# main_board_v1_0.net
KiCad netlist of a schematic drawn in EAGLE
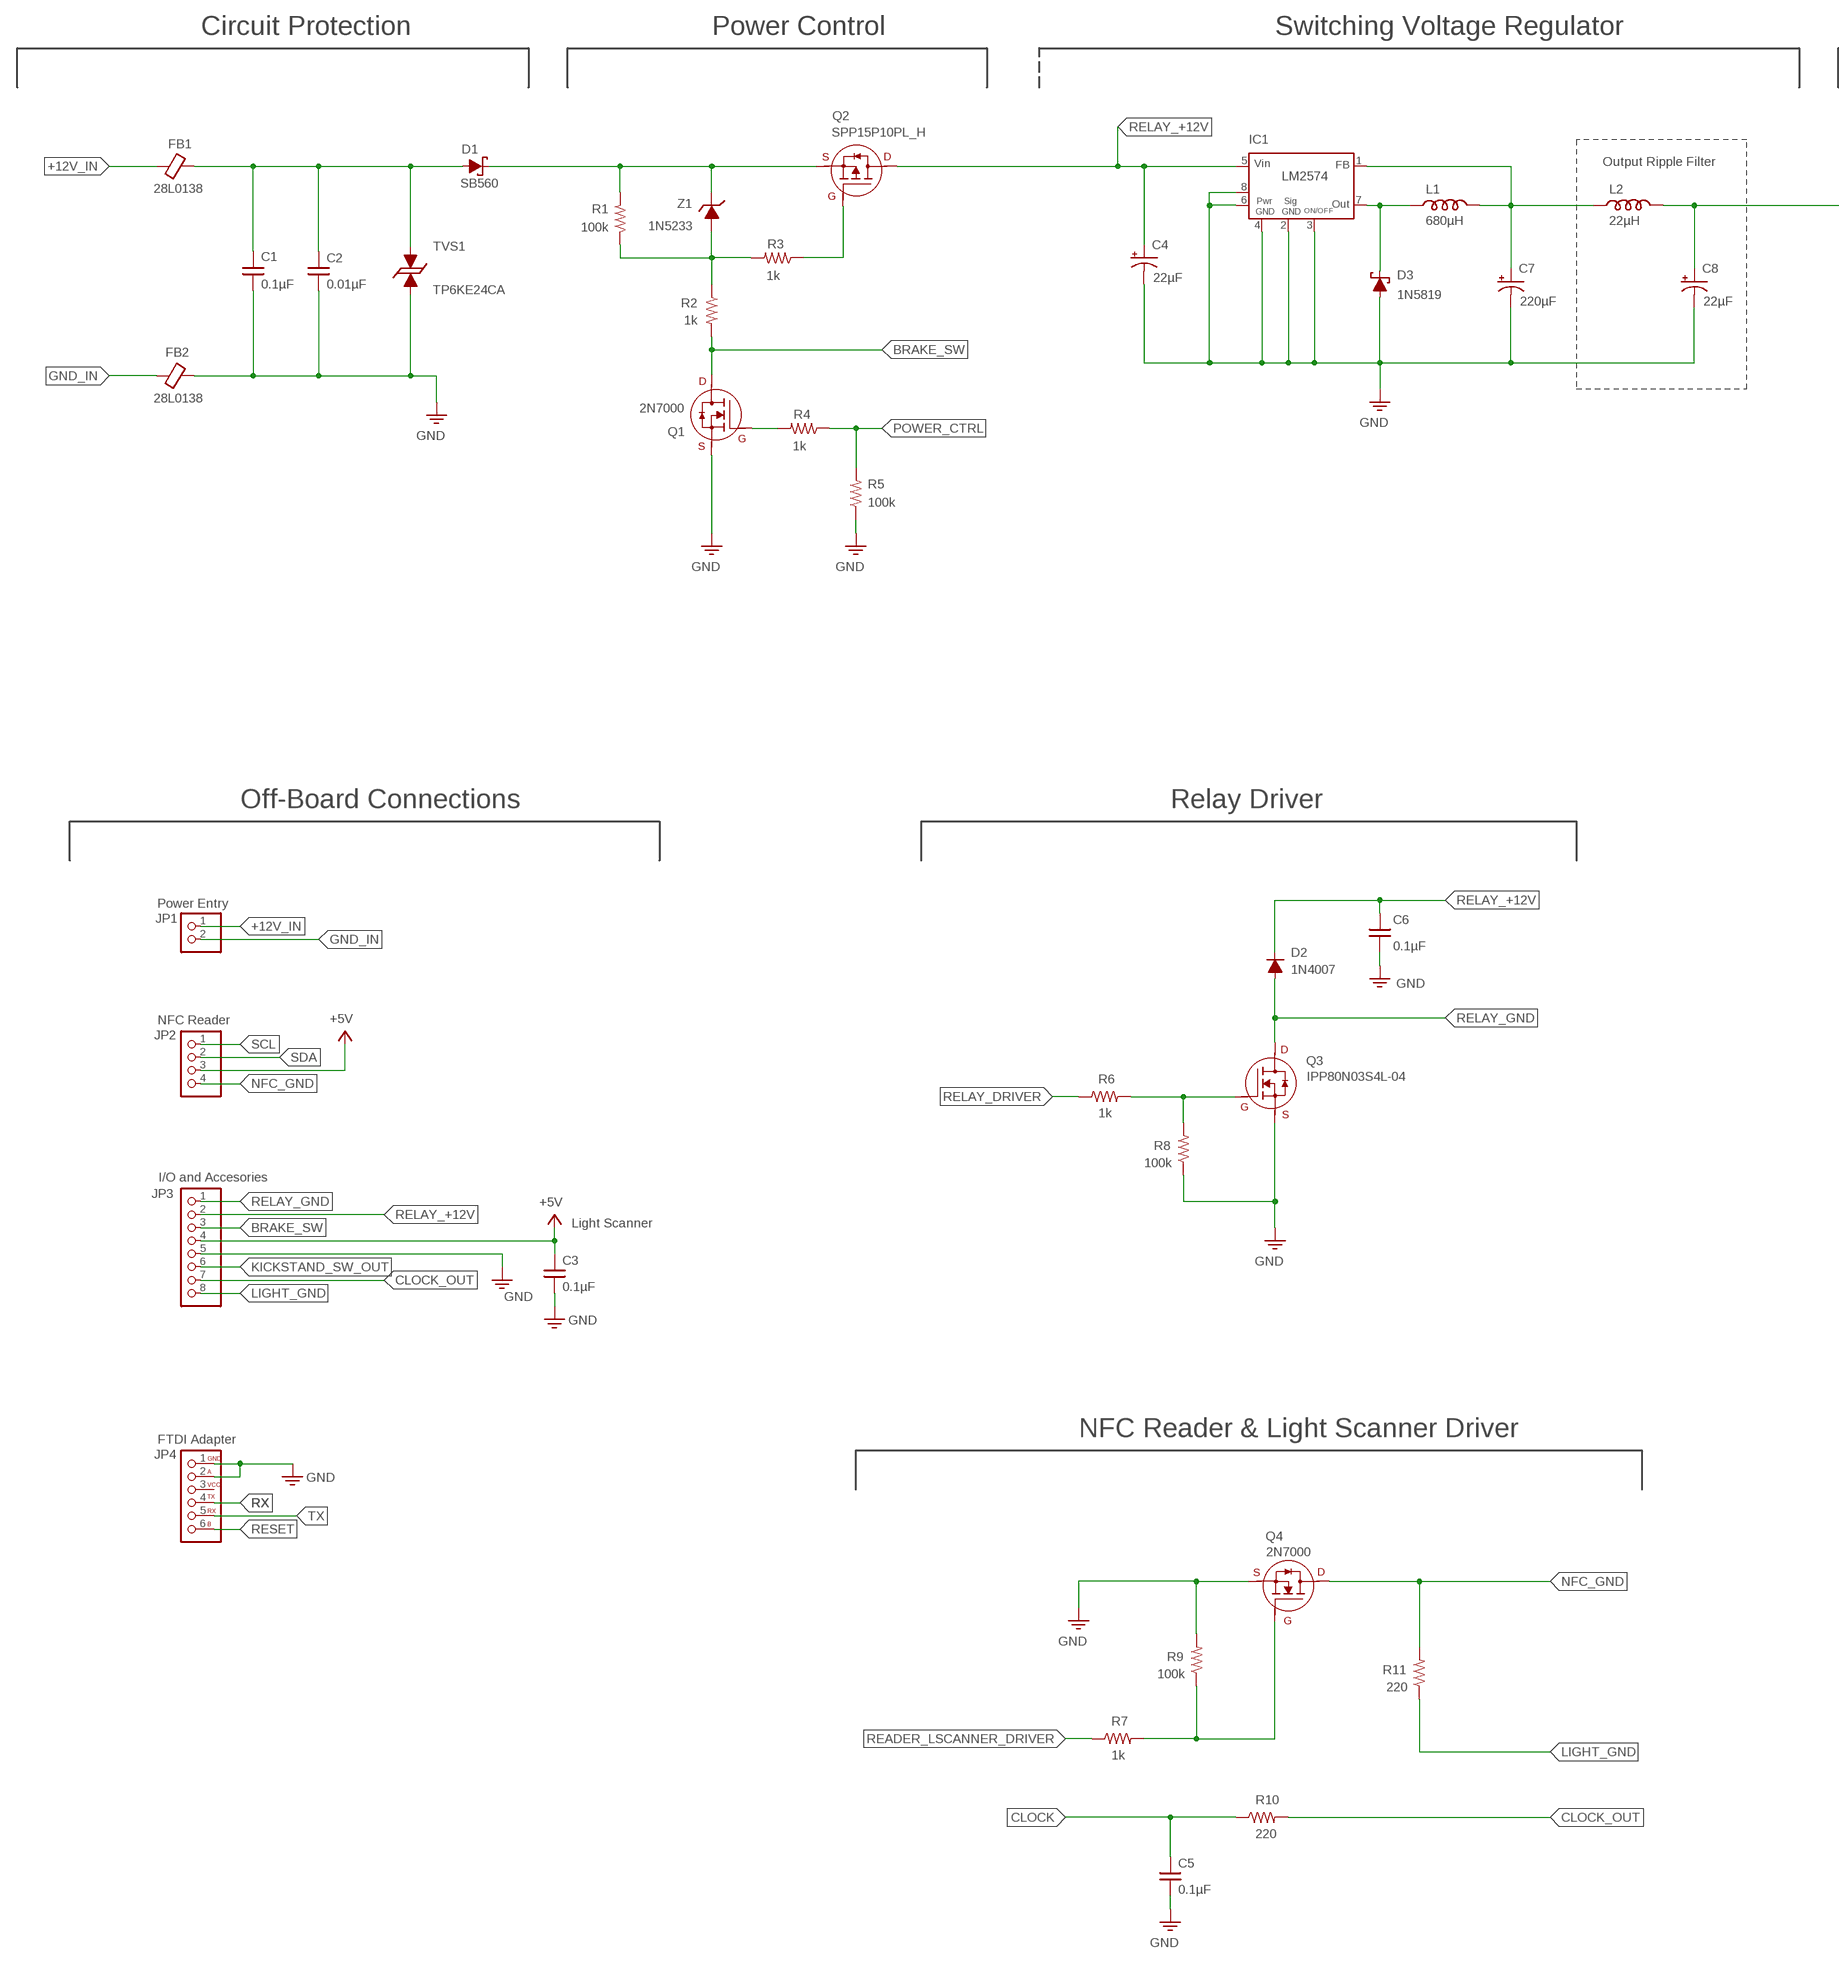
[diagram p0: schematic, sheet 1, part 1 of 2]
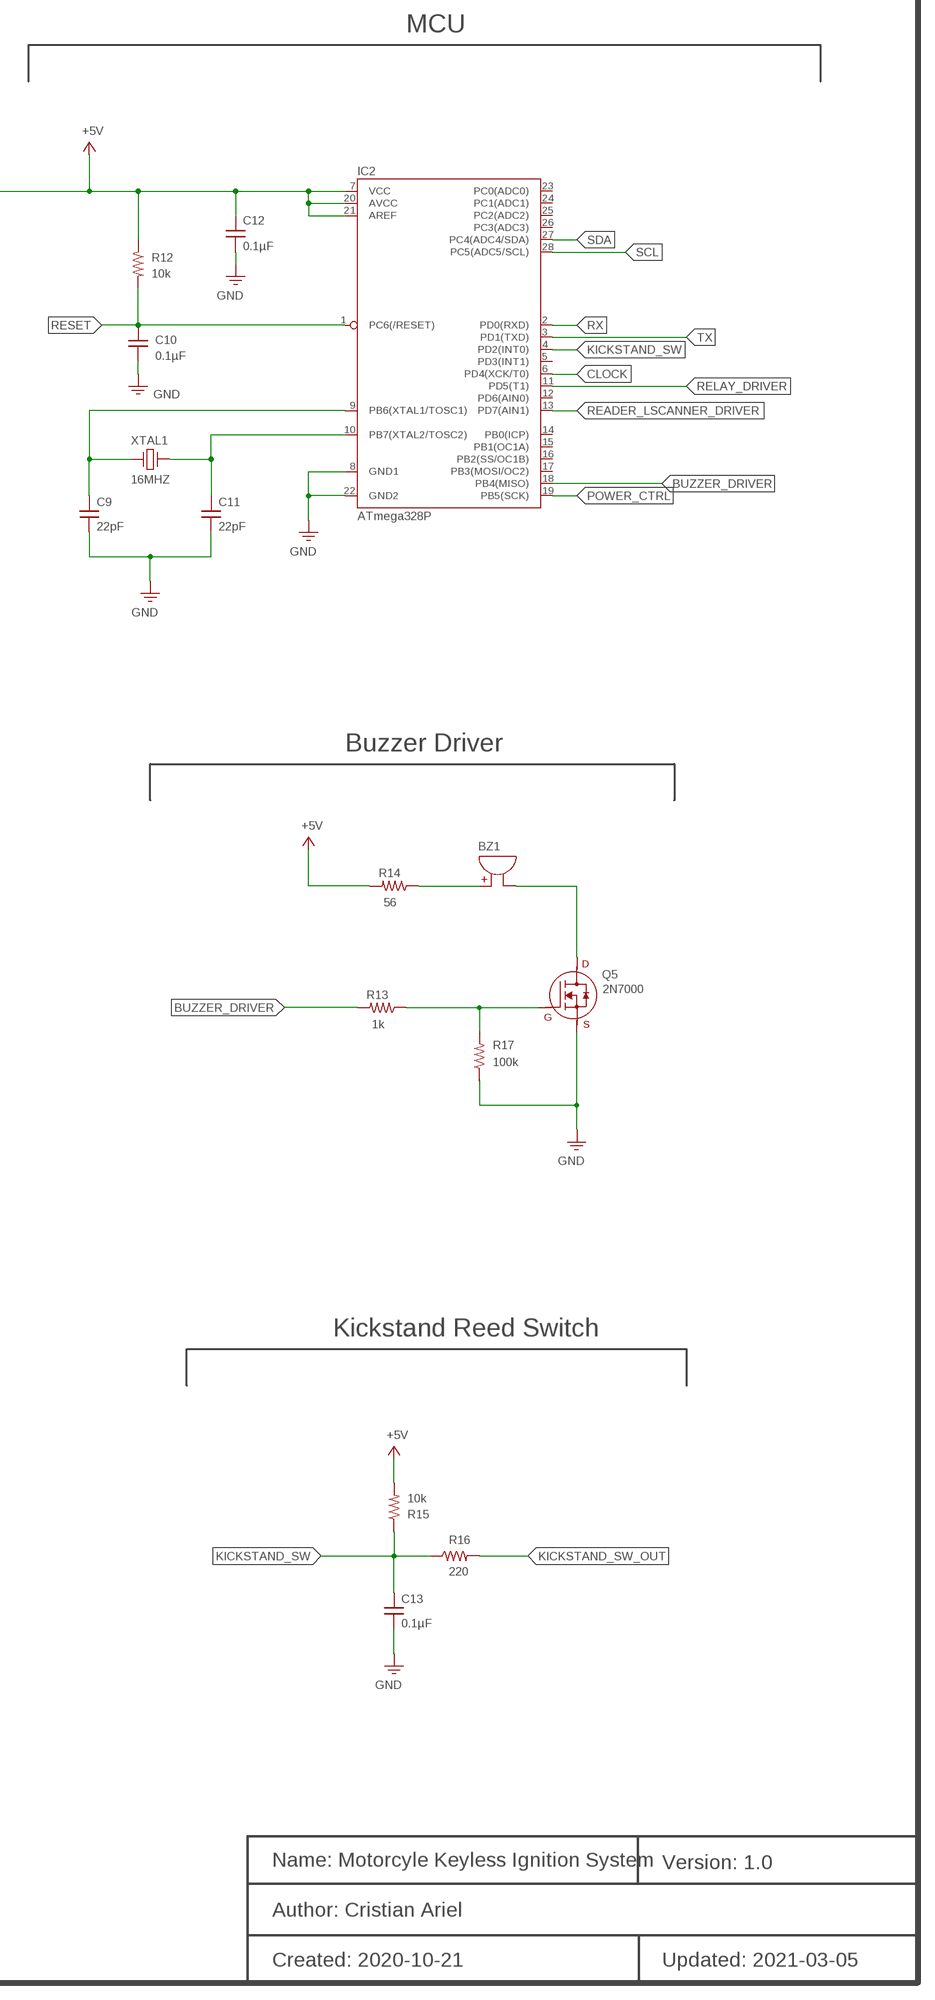
[diagram p1: schematic, sheet 1, part 2 of 2]

(export (version "E")
  (design (tool "Eeschema 10.0.6"))
  (components
    (comp (ref "BZ1")
      (value "BUZZER_254-EMB15-RO")
      (footprint "eagle-import:BUZZER-12")
      (libsource (lib "eagle-import") (part "BUZZER_254-EMB15-RO"))
    )
    (comp (ref "C1")
      (value "0.1µF")
      (footprint "eagle-import:C_H5")
      (libsource (lib "eagle-import") (part "C_K104K15X7RF53H5_0.1µF"))
    )
    (comp (ref "C2")
      (value "0.01µF")
      (footprint "eagle-import:C_H5")
      (libsource (lib "eagle-import") (part "C_FA24NP02E103JNU06_0.01µF"))
    )
    (comp (ref "C3")
      (value "0.1µF")
      (footprint "eagle-import:C_H5")
      (libsource (lib "eagle-import") (part "C_K104K15X7RF53H5_0.1µF"))
    )
    (comp (ref "C4")
      (value "22µF")
      (footprint "eagle-import:C_UBT_8")
      (libsource (lib "eagle-import") (part "C_POLARIZED_UBT1H220MPD_22µF"))
    )
    (comp (ref "C5")
      (value "0.1µF")
      (footprint "eagle-import:C_H5")
      (libsource (lib "eagle-import") (part "C_K104K15X7RF53H5_0.1µF"))
    )
    (comp (ref "C6")
      (value "0.1µF")
      (footprint "eagle-import:C_H5")
      (libsource (lib "eagle-import") (part "C_K104K15X7RF53H5_0.1µF"))
    )
    (comp (ref "C7")
      (value "220µF")
      (footprint "eagle-import:C_UBT_10")
      (libsource (lib "eagle-import") (part "C_POLARIZED_UBT1C221MPD_220µF"))
    )
    (comp (ref "C8")
      (value "22µF")
      (footprint "eagle-import:C_UBT_8")
      (libsource (lib "eagle-import") (part "C_POLARIZED_UBT1H220MPD_22µF"))
    )
    (comp (ref "C9")
      (value "22pF")
      (footprint "eagle-import:C_H5")
      (libsource (lib "eagle-import") (part "C_K220J10C0GF5UH5_22PF"))
    )
    (comp (ref "C10")
      (value "0.1µF")
      (footprint "eagle-import:C_H5")
      (libsource (lib "eagle-import") (part "C_K104K15X7RF53H5_0.1µF"))
    )
    (comp (ref "C11")
      (value "22pF")
      (footprint "eagle-import:C_H5")
      (libsource (lib "eagle-import") (part "C_K220J10C0GF5UH5_22PF"))
    )
    (comp (ref "C12")
      (value "0.1µF")
      (footprint "eagle-import:C_H5")
      (libsource (lib "eagle-import") (part "C_K104K15X7RF53H5_0.1µF"))
    )
    (comp (ref "C13")
      (value "0.1µF")
      (footprint "eagle-import:C_H5")
      (libsource (lib "eagle-import") (part "C_K104K15X7RF53H5_0.1µF"))
    )
    (comp (ref "D1")
      (value "SB560")
      (footprint "eagle-import:DO-201AD")
      (libsource (lib "eagle-import") (part "D_SCHOTTKY_SB560"))
    )
    (comp (ref "D2")
      (value "1N4007")
      (footprint "eagle-import:DO-41_(DO-204AL)")
      (libsource (lib "eagle-import") (part "D_1N4007"))
    )
    (comp (ref "D3")
      (value "1N5819")
      (footprint "eagle-import:DO-204AL_(DO-41)")
      (libsource (lib "eagle-import") (part "D_SCHOTTKY_1N5819"))
    )
    (comp (ref "FB1")
      (value "28L0138")
      (footprint "eagle-import:FB-5.23")
      (libsource (lib "eagle-import") (part "FERRITE_BEAD_28L0138"))
    )
    (comp (ref "FB2")
      (value "28L0138")
      (footprint "eagle-import:FB-5.23")
      (libsource (lib "eagle-import") (part "FERRITE_BEAD_28L0138"))
    )
    (comp (ref "IC1")
      (value "LM2574")
      (footprint "eagle-import:DIL08")
      (libsource (lib "eagle-import") (part "SWITCHING_REG_8_LM2574"))
    )
    (comp (ref "IC2")
      (value "ATmega328P")
      (footprint "eagle-import:DIP28")
      (libsource (lib "eagle-import") (part "ATMEGA328P_PDIP"))
    )
    (comp (ref "JP1")
      (value "Power Entry")
      (footprint "eagle-import:1X021")
      (libsource (lib "eagle-import") (part "PINHD-1X2"))
    )
    (comp (ref "JP2")
      (value "NFC Reader")
      (footprint "eagle-import:KK254_1X4")
      (libsource (lib "eagle-import") (part "KK254_1X4"))
    )
    (comp (ref "JP3")
      (value "I/O and Accesories")
      (footprint "eagle-import:1X08")
      (libsource (lib "eagle-import") (part "PINHD-1X8"))
    )
    (comp (ref "JP4")
      (value "FTDI Adapter")
      (footprint "eagle-import:1X06_FTDI")
      (libsource (lib "eagle-import") (part "FTDI_6"))
    )
    (comp (ref "L1")
      (value "680µH")
      (footprint "eagle-import:PE-526")
      (libsource (lib "eagle-import") (part "INDUCTOR_PE-52629NL_680µH"))
    )
    (comp (ref "L2")
      (value "22µH")
      (footprint "eagle-import:LTF-D")
      (libsource (lib "eagle-import") (part "INDUCTOR_LTF5022-D_22µH"))
    )
    (comp (ref "Q1")
      (value "2N7000")
      (footprint "eagle-import:TO-92")
      (libsource (lib "eagle-import") (part "MOSFET_NCH_V_2N7000"))
    )
    (comp (ref "Q2")
      (value "SPP15P10PL_H")
      (footprint "eagle-import:TO220")
      (libsource (lib "eagle-import") (part "MOSFET_PCH_H_SPP15P10PL_H"))
    )
    (comp (ref "Q3")
      (value "IPP80N03S4L-04")
      (footprint "eagle-import:TO220")
      (libsource (lib "eagle-import") (part "MOSFET_NCH_V_IPP80N03S4L-04"))
    )
    (comp (ref "Q4")
      (value "2N7000")
      (footprint "eagle-import:TO-92")
      (libsource (lib "eagle-import") (part "MOSFET_NCH_H_2N7000"))
    )
    (comp (ref "Q5")
      (value "2N7000")
      (footprint "eagle-import:TO-92")
      (libsource (lib "eagle-import") (part "MOSFET_NCH_V_2N7000"))
    )
    (comp (ref "R1")
      (value "100k")
      (footprint "eagle-import:R_THM")
      (libsource (lib "eagle-import") (part "R_THM"))
    )
    (comp (ref "R2")
      (value "1k")
      (footprint "eagle-import:R_THM")
      (libsource (lib "eagle-import") (part "R_THM"))
    )
    (comp (ref "R3")
      (value "1k")
      (footprint "eagle-import:R_THM")
      (libsource (lib "eagle-import") (part "R_THM"))
    )
    (comp (ref "R4")
      (value "1k")
      (footprint "eagle-import:R_THM")
      (libsource (lib "eagle-import") (part "R_THM"))
    )
    (comp (ref "R5")
      (value "100k")
      (footprint "eagle-import:R_THM")
      (libsource (lib "eagle-import") (part "R_THM"))
    )
    (comp (ref "R6")
      (value "1k")
      (footprint "eagle-import:R_THM")
      (libsource (lib "eagle-import") (part "R_THM"))
    )
    (comp (ref "R7")
      (value "1k")
      (footprint "eagle-import:R_THM")
      (libsource (lib "eagle-import") (part "R_THM"))
    )
    (comp (ref "R8")
      (value "100k")
      (footprint "eagle-import:R_THM")
      (libsource (lib "eagle-import") (part "R_THM"))
    )
    (comp (ref "R9")
      (value "100k")
      (footprint "eagle-import:R_THM")
      (libsource (lib "eagle-import") (part "R_THM"))
    )
    (comp (ref "R10")
      (value "220")
      (footprint "eagle-import:R_THM")
      (libsource (lib "eagle-import") (part "R_THM"))
    )
    (comp (ref "R11")
      (value "220")
      (footprint "eagle-import:R_THM")
      (libsource (lib "eagle-import") (part "R_THM"))
    )
    (comp (ref "R12")
      (value "10k")
      (footprint "eagle-import:R_THM")
      (libsource (lib "eagle-import") (part "R_THM"))
    )
    (comp (ref "R13")
      (value "1k")
      (footprint "eagle-import:R_THM")
      (libsource (lib "eagle-import") (part "R_THM"))
    )
    (comp (ref "R14")
      (value "56")
      (footprint "eagle-import:R_THM")
      (libsource (lib "eagle-import") (part "R_THM"))
    )
    (comp (ref "R15")
      (value "10k")
      (footprint "eagle-import:R_THM")
      (libsource (lib "eagle-import") (part "R_THM"))
    )
    (comp (ref "R16")
      (value "220")
      (footprint "eagle-import:R_THM")
      (libsource (lib "eagle-import") (part "R_THM"))
    )
    (comp (ref "R17")
      (value "100k")
      (footprint "eagle-import:R_THM")
      (libsource (lib "eagle-import") (part "R_THM"))
    )
    (comp (ref "TVS1")
      (value "TP6KE24CA")
      (footprint "eagle-import:DO-204AC_(DO-15)")
      (libsource (lib "eagle-import") (part "D_TVS_BI_P6KE24CA"))
    )
    (comp (ref "XTAL1")
      (value "16MHZ")
      (footprint "eagle-import:HC-49USX")
      (libsource (lib "eagle-import") (part "CRYSTAL_ECS-160-20-4X-DU_16MHZ"))
    )
    (comp (ref "Z1")
      (value "1N5233")
      (footprint "eagle-import:DO35-7A_ZENER")
      (libsource (lib "eagle-import") (part "D_ZENER_1N5233_6V"))
    )
  )
  (nets
    (net (code "1") (name "+5V") (class "Default")
      (node (ref "C12") (pin "1") (pinfunction "1_1") (pintype "passive"))
      (node (ref "C3") (pin "1") (pinfunction "1_1") (pintype "passive"))
      (node (ref "C8") (pin "+") (pinfunction "+_+") (pintype "passive"))
      (node (ref "IC2") (pin "20") (pinfunction "AVCC_20") (pintype "bidirectional"))
      (node (ref "IC2") (pin "21") (pinfunction "AREF_21") (pintype "bidirectional"))
      (node (ref "IC2") (pin "7") (pinfunction "VCC_7") (pintype "bidirectional"))
      (node (ref "JP2") (pin "3") (pinfunction "3_3") (pintype "passive"))
      (node (ref "JP3") (pin "4") (pinfunction "4_4") (pintype "passive"))
      (node (ref "L2") (pin "1") (pinfunction "END_1") (pintype "bidirectional"))
      (node (ref "R12") (pin "1") (pinfunction "1_1") (pintype "passive"))
      (node (ref "R14") (pin "2") (pinfunction "2_2") (pintype "passive"))
      (node (ref "R15") (pin "2") (pinfunction "2_2") (pintype "passive"))
    )
    (net (code "2") (name "+12V_IN") (class "Default")
      (node (ref "FB1") (pin "1") (pinfunction "1_1") (pintype "passive"))
      (node (ref "JP1") (pin "1") (pinfunction "1_1") (pintype "passive"))
    )
    (net (code "3") (name "BRAKE_SW") (class "Default")
      (node (ref "JP3") (pin "3") (pinfunction "3_3") (pintype "passive"))
      (node (ref "Q1") (pin "3") (pinfunction "D_3") (pintype "bidirectional"))
      (node (ref "R2") (pin "2") (pinfunction "2_2") (pintype "passive"))
    )
    (net (code "4") (name "BUZZER_DRIVER") (class "Default")
      (node (ref "IC2") (pin "18") (pinfunction "PB4(MISO)_18") (pintype "bidirectional"))
      (node (ref "R13") (pin "2") (pinfunction "2_2") (pintype "passive"))
    )
    (net (code "5") (name "CLOCK") (class "Default")
      (node (ref "C5") (pin "1") (pinfunction "1_1") (pintype "passive"))
      (node (ref "IC2") (pin "6") (pinfunction "PD4(XCK/T0)_6") (pintype "bidirectional"))
      (node (ref "R10") (pin "1") (pinfunction "1_1") (pintype "passive"))
    )
    (net (code "6") (name "CLOCK_OUT") (class "Default")
      (node (ref "JP3") (pin "7") (pinfunction "7_7") (pintype "passive"))
      (node (ref "R10") (pin "2") (pinfunction "2_2") (pintype "passive"))
    )
    (net (code "7") (name "GND") (class "Default")
      (node (ref "C1") (pin "2") (pinfunction "2_2") (pintype "passive"))
      (node (ref "C10") (pin "2") (pinfunction "2_2") (pintype "passive"))
      (node (ref "C11") (pin "2") (pinfunction "2_2") (pintype "passive"))
      (node (ref "C12") (pin "2") (pinfunction "2_2") (pintype "passive"))
      (node (ref "C13") (pin "2") (pinfunction "2_2") (pintype "passive"))
      (node (ref "C2") (pin "2") (pinfunction "2_2") (pintype "passive"))
      (node (ref "C3") (pin "2") (pinfunction "2_2") (pintype "passive"))
      (node (ref "C4") (pin "-") (pinfunction "-_-") (pintype "passive"))
      (node (ref "C5") (pin "2") (pinfunction "2_2") (pintype "passive"))
      (node (ref "C6") (pin "2") (pinfunction "2_2") (pintype "passive"))
      (node (ref "C7") (pin "-") (pinfunction "-_-") (pintype "passive"))
      (node (ref "C8") (pin "-") (pinfunction "-_-") (pintype "passive"))
      (node (ref "C9") (pin "2") (pinfunction "2_2") (pintype "passive"))
      (node (ref "D3") (pin "A") (pinfunction "A_A") (pintype "passive"))
      (node (ref "FB2") (pin "2") (pinfunction "2_2") (pintype "passive"))
      (node (ref "IC1") (pin "2") (pinfunction "SIG_GND_2") (pintype "bidirectional"))
      (node (ref "IC1") (pin "3") (pinfunction "ON/OFF_3") (pintype "bidirectional"))
      (node (ref "IC1") (pin "4") (pinfunction "PWR_GND_4") (pintype "bidirectional"))
      (node (ref "IC1") (pin "6") (pinfunction "P$1_6") (pintype "bidirectional"))
      (node (ref "IC1") (pin "8") (pinfunction "P$2_8") (pintype "bidirectional"))
      (node (ref "IC2") (pin "22") (pinfunction "GND2_22") (pintype "bidirectional"))
      (node (ref "IC2") (pin "8") (pinfunction "GND1_8") (pintype "bidirectional"))
      (node (ref "JP3") (pin "5") (pinfunction "5_5") (pintype "passive"))
      (node (ref "JP4") (pin "1") (pinfunction "1_1") (pintype "passive"))
      (node (ref "JP4") (pin "2") (pinfunction "2_2") (pintype "passive"))
      (node (ref "Q1") (pin "1") (pinfunction "S_1") (pintype "bidirectional"))
      (node (ref "Q3") (pin "3") (pinfunction "S_3") (pintype "bidirectional"))
      (node (ref "Q4") (pin "1") (pinfunction "S_1") (pintype "bidirectional"))
      (node (ref "Q5") (pin "1") (pinfunction "S_1") (pintype "bidirectional"))
      (node (ref "R17") (pin "1") (pinfunction "1_1") (pintype "passive"))
      (node (ref "R5") (pin "1") (pinfunction "1_1") (pintype "passive"))
      (node (ref "R8") (pin "1") (pinfunction "1_1") (pintype "passive"))
      (node (ref "R9") (pin "2") (pinfunction "2_2") (pintype "passive"))
      (node (ref "TVS1") (pin "2") (pinfunction "2_2") (pintype "passive"))
    )
    (net (code "8") (name "GND_IN") (class "Default")
      (node (ref "FB2") (pin "1") (pinfunction "1_1") (pintype "passive"))
      (node (ref "JP1") (pin "2") (pinfunction "2_2") (pintype "passive"))
    )
    (net (code "9") (name "KICKSTAND_SW") (class "Default")
      (node (ref "C13") (pin "1") (pinfunction "1_1") (pintype "passive"))
      (node (ref "IC2") (pin "4") (pinfunction "PD2(INT0)_4") (pintype "bidirectional"))
      (node (ref "R15") (pin "1") (pinfunction "1_1") (pintype "passive"))
      (node (ref "R16") (pin "1") (pinfunction "1_1") (pintype "passive"))
    )
    (net (code "10") (name "KICKSTAND_SW_OUT") (class "Default")
      (node (ref "JP3") (pin "6") (pinfunction "6_6") (pintype "passive"))
      (node (ref "R16") (pin "2") (pinfunction "2_2") (pintype "passive"))
    )
    (net (code "11") (name "LIGHT_GND") (class "Default")
      (node (ref "JP3") (pin "8") (pinfunction "8_8") (pintype "passive"))
      (node (ref "R11") (pin "1") (pinfunction "1_1") (pintype "passive"))
    )
    (net (code "12") (name "NFC_GND") (class "Default")
      (node (ref "JP2") (pin "4") (pinfunction "4_4") (pintype "passive"))
      (node (ref "Q4") (pin "3") (pinfunction "D_3") (pintype "bidirectional"))
      (node (ref "R11") (pin "2") (pinfunction "2_2") (pintype "passive"))
    )
    (net (code "13") (name "Net-(BZ1-Pad+)") (class "Default")
      (node (ref "BZ1") (pin "+") (pinfunction "+_+") (pintype "passive"))
      (node (ref "R14") (pin "1") (pinfunction "1_1") (pintype "passive"))
    )
    (net (code "14") (name "Net-(C1-Pad1)") (class "Default")
      (node (ref "C1") (pin "1") (pinfunction "1_1") (pintype "passive"))
      (node (ref "C2") (pin "1") (pinfunction "1_1") (pintype "passive"))
      (node (ref "D1") (pin "A") (pinfunction "A_A") (pintype "passive"))
      (node (ref "FB1") (pin "2") (pinfunction "2_2") (pintype "passive"))
      (node (ref "TVS1") (pin "1") (pinfunction "1_1") (pintype "passive"))
    )
    (net (code "15") (name "Net-(IC1-FB)") (class "Default")
      (node (ref "C7") (pin "+") (pinfunction "+_+") (pintype "passive"))
      (node (ref "IC1") (pin "1") (pinfunction "FB_1") (pintype "bidirectional"))
      (node (ref "L1") (pin "2") (pinfunction "END_2") (pintype "bidirectional"))
      (node (ref "L2") (pin "2") (pinfunction "START_2") (pintype "bidirectional"))
    )
    (net (code "16") (name "Net-(IC1-OUT)") (class "Default")
      (node (ref "D3") (pin "C") (pinfunction "C_C") (pintype "passive"))
      (node (ref "IC1") (pin "7") (pinfunction "OUT_7") (pintype "bidirectional"))
      (node (ref "L1") (pin "1") (pinfunction "START_1") (pintype "bidirectional"))
    )
    (net (code "17") (name "Net-(IC2-PB6(XTAL1{slash}TOSC1))") (class "Default")
      (node (ref "C9") (pin "1") (pinfunction "1_1") (pintype "passive"))
      (node (ref "IC2") (pin "9") (pinfunction "PB6(XTAL1/TOSC1)_9") (pintype "bidirectional"))
      (node (ref "XTAL1") (pin "1") (pinfunction "1_1") (pintype "passive"))
    )
    (net (code "18") (name "Net-(IC2-PB7(XTAL2{slash}TOSC2))") (class "Default")
      (node (ref "C11") (pin "1") (pinfunction "1_1") (pintype "passive"))
      (node (ref "IC2") (pin "10") (pinfunction "PB7(XTAL2/TOSC2)_10") (pintype "bidirectional"))
      (node (ref "XTAL1") (pin "2") (pinfunction "2_2") (pintype "passive"))
    )
    (net (code "19") (name "Net-(Q1-G)") (class "Default")
      (node (ref "Q1") (pin "2") (pinfunction "G_2") (pintype "bidirectional"))
      (node (ref "R4") (pin "2") (pinfunction "2_2") (pintype "passive"))
    )
    (net (code "20") (name "Net-(Q2-G)") (class "Default")
      (node (ref "Q2") (pin "1") (pinfunction "G_1") (pintype "bidirectional"))
      (node (ref "R3") (pin "1") (pinfunction "1_1") (pintype "passive"))
    )
    (net (code "21") (name "Net-(Q2-S)") (class "Default")
      (node (ref "D1") (pin "C") (pinfunction "C_C") (pintype "passive"))
      (node (ref "Q2") (pin "3") (pinfunction "S_3") (pintype "bidirectional"))
      (node (ref "R1") (pin "2") (pinfunction "2_2") (pintype "passive"))
      (node (ref "Z1") (pin "C") (pinfunction "C_C") (pintype "passive"))
    )
    (net (code "22") (name "Net-(Q3-G)") (class "Default")
      (node (ref "Q3") (pin "1") (pinfunction "G_1") (pintype "bidirectional"))
      (node (ref "R6") (pin "2") (pinfunction "2_2") (pintype "passive"))
      (node (ref "R8") (pin "2") (pinfunction "2_2") (pintype "passive"))
    )
    (net (code "23") (name "Net-(Q4-G)") (class "Default")
      (node (ref "Q4") (pin "2") (pinfunction "G_2") (pintype "bidirectional"))
      (node (ref "R7") (pin "2") (pinfunction "2_2") (pintype "passive"))
      (node (ref "R9") (pin "1") (pinfunction "1_1") (pintype "passive"))
    )
    (net (code "24") (name "Net-(Q5-D)") (class "Default")
      (node (ref "BZ1") (pin "-") (pinfunction "-_-") (pintype "passive"))
      (node (ref "Q5") (pin "3") (pinfunction "D_3") (pintype "bidirectional"))
    )
    (net (code "25") (name "Net-(Q5-G)") (class "Default")
      (node (ref "Q5") (pin "2") (pinfunction "G_2") (pintype "bidirectional"))
      (node (ref "R13") (pin "1") (pinfunction "1_1") (pintype "passive"))
      (node (ref "R17") (pin "2") (pinfunction "2_2") (pintype "passive"))
    )
    (net (code "26") (name "Net-(R1-Pad1)") (class "Default")
      (node (ref "R1") (pin "1") (pinfunction "1_1") (pintype "passive"))
      (node (ref "R2") (pin "1") (pinfunction "1_1") (pintype "passive"))
      (node (ref "R3") (pin "2") (pinfunction "2_2") (pintype "passive"))
      (node (ref "Z1") (pin "A") (pinfunction "A_A") (pintype "passive"))
    )
    (net (code "27") (name "POWER_CTRL") (class "Default")
      (node (ref "IC2") (pin "19") (pinfunction "PB5(SCK)_19") (pintype "bidirectional"))
      (node (ref "R4") (pin "1") (pinfunction "1_1") (pintype "passive"))
      (node (ref "R5") (pin "2") (pinfunction "2_2") (pintype "passive"))
    )
    (net (code "28") (name "READER_LSCANNER_DRIVER") (class "Default")
      (node (ref "IC2") (pin "13") (pinfunction "PD7(AIN1)_13") (pintype "bidirectional"))
      (node (ref "R7") (pin "1") (pinfunction "1_1") (pintype "passive"))
    )
    (net (code "29") (name "RELAY_+12V") (class "Default")
      (node (ref "C4") (pin "+") (pinfunction "+_+") (pintype "passive"))
      (node (ref "C6") (pin "1") (pinfunction "1_1") (pintype "passive"))
      (node (ref "D2") (pin "C") (pinfunction "C_C") (pintype "passive"))
      (node (ref "IC1") (pin "5") (pinfunction "VIN_5") (pintype "power_in"))
      (node (ref "JP3") (pin "2") (pinfunction "2_2") (pintype "passive"))
      (node (ref "Q2") (pin "2") (pinfunction "D_2") (pintype "bidirectional"))
    )
    (net (code "30") (name "RELAY_DRIVER") (class "Default")
      (node (ref "IC2") (pin "11") (pinfunction "PD5(T1)_11") (pintype "bidirectional"))
      (node (ref "R6") (pin "1") (pinfunction "1_1") (pintype "passive"))
    )
    (net (code "31") (name "RELAY_GND") (class "Default")
      (node (ref "D2") (pin "A") (pinfunction "A_A") (pintype "passive"))
      (node (ref "JP3") (pin "1") (pinfunction "1_1") (pintype "passive"))
      (node (ref "Q3") (pin "2") (pinfunction "D_2") (pintype "bidirectional"))
    )
    (net (code "32") (name "RESET") (class "Default")
      (node (ref "C10") (pin "1") (pinfunction "1_1") (pintype "passive"))
      (node (ref "IC2") (pin "1") (pinfunction "PC6(/RESET)_1") (pintype "bidirectional"))
      (node (ref "JP4") (pin "6") (pinfunction "6_6") (pintype "passive"))
      (node (ref "R12") (pin "2") (pinfunction "2_2") (pintype "passive"))
    )
    (net (code "33") (name "RX") (class "Default")
      (node (ref "IC2") (pin "2") (pinfunction "PD0(RXD)_2") (pintype "bidirectional"))
      (node (ref "JP4") (pin "4") (pinfunction "4_4") (pintype "passive"))
    )
    (net (code "34") (name "SCL") (class "Default")
      (node (ref "IC2") (pin "28") (pinfunction "PC5(ADC5/SCL)_28") (pintype "bidirectional"))
      (node (ref "JP2") (pin "1") (pinfunction "1_1") (pintype "passive"))
    )
    (net (code "35") (name "SDA") (class "Default")
      (node (ref "IC2") (pin "27") (pinfunction "PC4(ADC4/SDA)_27") (pintype "bidirectional"))
      (node (ref "JP2") (pin "2") (pinfunction "2_2") (pintype "passive"))
    )
    (net (code "36") (name "TX") (class "Default")
      (node (ref "IC2") (pin "3") (pinfunction "PD1(TXD)_3") (pintype "bidirectional"))
      (node (ref "JP4") (pin "5") (pinfunction "5_5") (pintype "passive"))
    )
    (net (code "37") (name "unconnected-(IC2-PB0(ICP)-Pad14)") (class "Default")
      (node (ref "IC2") (pin "14") (pinfunction "PB0(ICP)_14") (pintype "bidirectional"))
    )
    (net (code "38") (name "unconnected-(IC2-PB1(OC1A)-Pad15)") (class "Default")
      (node (ref "IC2") (pin "15") (pinfunction "PB1(OC1A)_15") (pintype "bidirectional"))
    )
    (net (code "39") (name "unconnected-(IC2-PB2(SS{slash}OC1B)-Pad16)") (class "Default")
      (node (ref "IC2") (pin "16") (pinfunction "PB2(SS/OC1B)_16") (pintype "bidirectional"))
    )
    (net (code "40") (name "unconnected-(IC2-PB3(MOSI{slash}OC2)-Pad17)") (class "Default")
      (node (ref "IC2") (pin "17") (pinfunction "PB3(MOSI/OC2)_17") (pintype "bidirectional"))
    )
    (net (code "41") (name "unconnected-(IC2-PC0(ADC0)-Pad23)") (class "Default")
      (node (ref "IC2") (pin "23") (pinfunction "PC0(ADC0)_23") (pintype "bidirectional"))
    )
    (net (code "42") (name "unconnected-(IC2-PC1(ADC1)-Pad24)") (class "Default")
      (node (ref "IC2") (pin "24") (pinfunction "PC1(ADC1)_24") (pintype "bidirectional"))
    )
    (net (code "43") (name "unconnected-(IC2-PC2(ADC2)-Pad25)") (class "Default")
      (node (ref "IC2") (pin "25") (pinfunction "PC2(ADC2)_25") (pintype "bidirectional"))
    )
    (net (code "44") (name "unconnected-(IC2-PC3(ADC3)-Pad26)") (class "Default")
      (node (ref "IC2") (pin "26") (pinfunction "PC3(ADC3)_26") (pintype "bidirectional"))
    )
    (net (code "45") (name "unconnected-(IC2-PD3(INT1)-Pad5)") (class "Default")
      (node (ref "IC2") (pin "5") (pinfunction "PD3(INT1)_5") (pintype "bidirectional"))
    )
    (net (code "46") (name "unconnected-(IC2-PD6(AIN0)-Pad12)") (class "Default")
      (node (ref "IC2") (pin "12") (pinfunction "PD6(AIN0)_12") (pintype "bidirectional"))
    )
    (net (code "47") (name "unconnected-(JP4-Pad3)") (class "Default")
      (node (ref "JP4") (pin "3") (pinfunction "3_3") (pintype "passive"))
    )
  )
)
